# WalkerStalkerv0.net
KiCad netlist of a schematic drawn in EAGLE
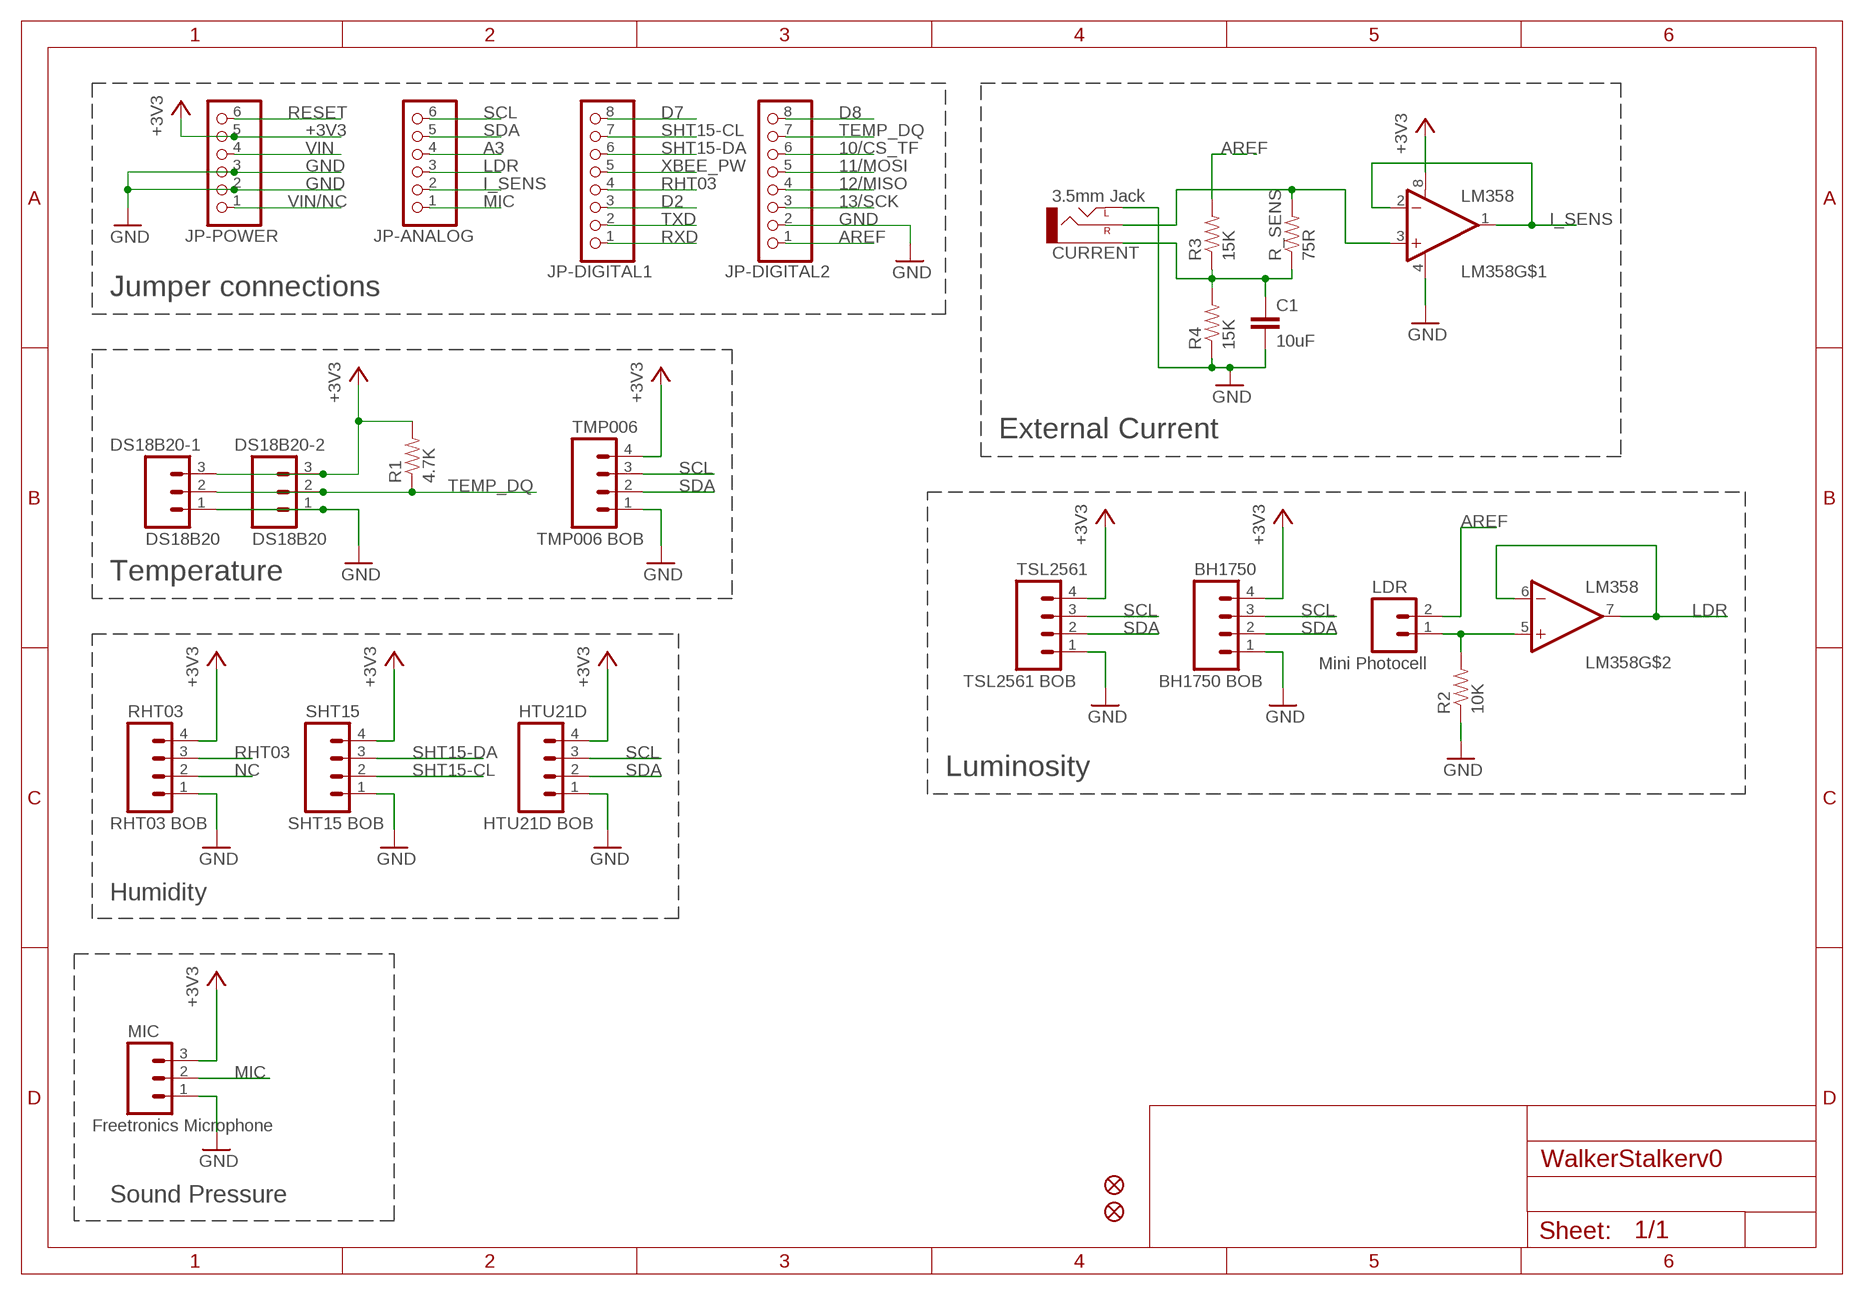
[diagram p0: schematic, sheet 1]

(export (version "E")
  (design (tool "Eeschema 10.0.6"))
  (components
    (comp (ref "BH1750")
      (value "BH1750 BOB")
      (footprint "eagle-import:MOLEX-1X4")
      (libsource (lib "eagle-import") (part "M04POLAR"))
    )
    (comp (ref "C1")
      (value "10uF")
      (footprint "eagle-import:1206")
      (libsource (lib "eagle-import") (part "CAP1206"))
    )
    (comp (ref "CURRENT")
      (value "3.5mm Jack")
      (footprint "eagle-import:AUDIO-JACK")
      (libsource (lib "eagle-import") (part "AUDIO-JACKPTH"))
    )
    (comp (ref "DS18B20-1")
      (value "DS18B20")
      (footprint "eagle-import:MOLEX-1X3")
      (libsource (lib "eagle-import") (part "M03POLAR"))
    )
    (comp (ref "DS18B20-2")
      (value "DS18B20")
      (footprint "eagle-import:MOLEX-1X3")
      (libsource (lib "eagle-import") (part "M03POLAR"))
    )
    (comp (ref "FID1")
      (value "FIDUCIAL1.5X3")
      (footprint "eagle-import:FIDUCIAL-1.5X3")
      (libsource (lib "eagle-import") (part "FIDUCIAL1.5X3"))
    )
    (comp (ref "FID2")
      (value "FIDUCIAL1.5X3")
      (footprint "eagle-import:FIDUCIAL-1.5X3")
      (libsource (lib "eagle-import") (part "FIDUCIAL1.5X3"))
    )
    (comp (ref "HTU21D")
      (value "HTU21D BOB")
      (footprint "eagle-import:MOLEX-1X4")
      (libsource (lib "eagle-import") (part "M04POLAR"))
    )
    (comp (ref "JP-ANALOG")
      (value "PINHD-1X6CB")
      (footprint "eagle-import:1X06-CLEANBIG")
      (libsource (lib "eagle-import") (part "PINHD-1X6CB"))
    )
    (comp (ref "JP-DIGITAL1")
      (value "PINHD-1X8CLEANBIG")
      (footprint "eagle-import:1X08-CLEANBIG")
      (libsource (lib "eagle-import") (part "PINHD-1X8CLEANBIG"))
    )
    (comp (ref "JP-DIGITAL2")
      (value "PINHD-1X8CLEANBIG")
      (footprint "eagle-import:1X08-CLEANBIG")
      (libsource (lib "eagle-import") (part "PINHD-1X8CLEANBIG"))
    )
    (comp (ref "JP-POWER")
      (value "PINHD-1X6CB")
      (footprint "eagle-import:1X06-CLEANBIG")
      (libsource (lib "eagle-import") (part "PINHD-1X6CB"))
    )
    (comp (ref "LDR")
      (value "Mini Photocell")
      (footprint "eagle-import:MOLEX-1X2")
      (libsource (lib "eagle-import") (part "M02POLAR"))
    )
    (comp (ref "LM358")
      (value "LM358")
      (footprint "eagle-import:DIP08")
      (libsource (lib "eagle-import") (part "LM358"))
    )
    (comp (ref "MIC")
      (value "Freetronics Microphone")
      (footprint "eagle-import:MOLEX-1X3")
      (libsource (lib "eagle-import") (part "M03POLAR"))
    )
    (comp (ref "R1")
      (value "4.7K")
      (footprint "eagle-import:1206")
      (libsource (lib "eagle-import") (part "RESISTOR1206"))
    )
    (comp (ref "R2")
      (value "10K")
      (footprint "eagle-import:1206")
      (libsource (lib "eagle-import") (part "RESISTOR1206"))
    )
    (comp (ref "R3")
      (value "15K")
      (footprint "eagle-import:1206")
      (libsource (lib "eagle-import") (part "RESISTOR1206"))
    )
    (comp (ref "R4")
      (value "15K")
      (footprint "eagle-import:1206")
      (libsource (lib "eagle-import") (part "RESISTOR1206"))
    )
    (comp (ref "RHT03")
      (value "RHT03 BOB")
      (footprint "eagle-import:MOLEX-1X4")
      (libsource (lib "eagle-import") (part "M04POLAR"))
    )
    (comp (ref "R_SENS")
      (value "75R")
      (footprint "eagle-import:1206")
      (libsource (lib "eagle-import") (part "RESISTOR1206"))
    )
    (comp (ref "SHT15")
      (value "SHT15 BOB")
      (footprint "eagle-import:MOLEX-1X4")
      (libsource (lib "eagle-import") (part "M04POLAR"))
    )
    (comp (ref "TMP006")
      (value "TMP006 BOB")
      (footprint "eagle-import:MOLEX-1X4")
      (libsource (lib "eagle-import") (part "M04POLAR"))
    )
    (comp (ref "TSL2561")
      (value "TSL2561 BOB")
      (footprint "eagle-import:MOLEX-1X4")
      (libsource (lib "eagle-import") (part "M04POLAR"))
    )
  )
  (nets
    (net (code "1") (name "+3V3") (class "Default")
      (node (ref "BH1750") (pin "4") (pinfunction "4_4") (pintype "passive"))
      (node (ref "DS18B20-1") (pin "3") (pinfunction "3_3") (pintype "passive"))
      (node (ref "DS18B20-2") (pin "3") (pinfunction "3_3") (pintype "passive"))
      (node (ref "HTU21D") (pin "4") (pinfunction "4_4") (pintype "passive"))
      (node (ref "JP-POWER") (pin "5") (pinfunction "5_5") (pintype "passive"))
      (node (ref "LM358") (pin "8") (pinfunction "V+_8") (pintype "power_in"))
      (node (ref "MIC") (pin "3") (pinfunction "3_3") (pintype "passive"))
      (node (ref "R1") (pin "2") (pinfunction "2_2") (pintype "passive"))
      (node (ref "RHT03") (pin "4") (pinfunction "4_4") (pintype "passive"))
      (node (ref "SHT15") (pin "4") (pinfunction "4_4") (pintype "passive"))
      (node (ref "TMP006") (pin "4") (pinfunction "4_4") (pintype "passive"))
      (node (ref "TSL2561") (pin "4") (pinfunction "4_4") (pintype "passive"))
    )
    (net (code "2") (name "/10{slash}CS_TF") (class "Default")
      (node (ref "JP-DIGITAL2") (pin "6") (pinfunction "6_6") (pintype "passive"))
    )
    (net (code "3") (name "/11{slash}MOSI") (class "Default")
      (node (ref "JP-DIGITAL2") (pin "5") (pinfunction "5_5") (pintype "passive"))
    )
    (net (code "4") (name "/12{slash}MISO") (class "Default")
      (node (ref "JP-DIGITAL2") (pin "4") (pinfunction "4_4") (pintype "passive"))
    )
    (net (code "5") (name "/13{slash}SCK") (class "Default")
      (node (ref "JP-DIGITAL2") (pin "3") (pinfunction "3_3") (pintype "passive"))
    )
    (net (code "6") (name "/A3") (class "Default")
      (node (ref "JP-ANALOG") (pin "4") (pinfunction "4_4") (pintype "passive"))
    )
    (net (code "7") (name "/AREF") (class "Default")
      (node (ref "JP-DIGITAL2") (pin "1") (pinfunction "1_1") (pintype "passive"))
      (node (ref "LDR") (pin "2") (pinfunction "2_2") (pintype "passive"))
      (node (ref "R3") (pin "2") (pinfunction "2_2") (pintype "passive"))
    )
    (net (code "8") (name "/D2") (class "Default")
      (node (ref "JP-DIGITAL1") (pin "3") (pinfunction "3_3") (pintype "passive"))
    )
    (net (code "9") (name "/D7") (class "Default")
      (node (ref "JP-DIGITAL1") (pin "8") (pinfunction "8_8") (pintype "passive"))
    )
    (net (code "10") (name "/D8") (class "Default")
      (node (ref "JP-DIGITAL2") (pin "8") (pinfunction "8_8") (pintype "passive"))
    )
    (net (code "11") (name "/I_SENS") (class "Default")
      (node (ref "JP-ANALOG") (pin "2") (pinfunction "2_2") (pintype "passive"))
      (node (ref "LM358") (pin "1") (pinfunction "OUT_1") (pintype "output"))
      (node (ref "LM358") (pin "2") (pinfunction "-IN_2") (pintype "input"))
    )
    (net (code "12") (name "/LDR") (class "Default")
      (node (ref "JP-ANALOG") (pin "3") (pinfunction "3_3") (pintype "passive"))
      (node (ref "LM358") (pin "6") (pinfunction "-IN_6") (pintype "input"))
      (node (ref "LM358") (pin "7") (pinfunction "OUT_7") (pintype "output"))
    )
    (net (code "13") (name "/MIC") (class "Default")
      (node (ref "JP-ANALOG") (pin "1") (pinfunction "1_1") (pintype "passive"))
      (node (ref "MIC") (pin "2") (pinfunction "2_2") (pintype "passive"))
    )
    (net (code "14") (name "/NC") (class "Default")
      (node (ref "RHT03") (pin "2") (pinfunction "2_2") (pintype "passive"))
    )
    (net (code "15") (name "/RESET") (class "Default")
      (node (ref "JP-POWER") (pin "6") (pinfunction "6_6") (pintype "passive"))
    )
    (net (code "16") (name "/RHT03") (class "Default")
      (node (ref "JP-DIGITAL1") (pin "4") (pinfunction "4_4") (pintype "passive"))
      (node (ref "RHT03") (pin "3") (pinfunction "3_3") (pintype "passive"))
    )
    (net (code "17") (name "/RXD") (class "Default")
      (node (ref "JP-DIGITAL1") (pin "1") (pinfunction "1_1") (pintype "passive"))
    )
    (net (code "18") (name "/SCL") (class "Default")
      (node (ref "BH1750") (pin "3") (pinfunction "3_3") (pintype "passive"))
      (node (ref "HTU21D") (pin "3") (pinfunction "3_3") (pintype "passive"))
      (node (ref "JP-ANALOG") (pin "6") (pinfunction "6_6") (pintype "passive"))
      (node (ref "TMP006") (pin "3") (pinfunction "3_3") (pintype "passive"))
      (node (ref "TSL2561") (pin "3") (pinfunction "3_3") (pintype "passive"))
    )
    (net (code "19") (name "/SDA") (class "Default")
      (node (ref "BH1750") (pin "2") (pinfunction "2_2") (pintype "passive"))
      (node (ref "HTU21D") (pin "2") (pinfunction "2_2") (pintype "passive"))
      (node (ref "JP-ANALOG") (pin "5") (pinfunction "5_5") (pintype "passive"))
      (node (ref "TMP006") (pin "2") (pinfunction "2_2") (pintype "passive"))
      (node (ref "TSL2561") (pin "2") (pinfunction "2_2") (pintype "passive"))
    )
    (net (code "20") (name "/SHT15-CL") (class "Default")
      (node (ref "JP-DIGITAL1") (pin "7") (pinfunction "7_7") (pintype "passive"))
      (node (ref "SHT15") (pin "2") (pinfunction "2_2") (pintype "passive"))
    )
    (net (code "21") (name "/SHT15-DA") (class "Default")
      (node (ref "JP-DIGITAL1") (pin "6") (pinfunction "6_6") (pintype "passive"))
      (node (ref "SHT15") (pin "3") (pinfunction "3_3") (pintype "passive"))
    )
    (net (code "22") (name "/TEMP_DQ") (class "Default")
      (node (ref "DS18B20-1") (pin "2") (pinfunction "2_2") (pintype "passive"))
      (node (ref "DS18B20-2") (pin "2") (pinfunction "2_2") (pintype "passive"))
      (node (ref "JP-DIGITAL2") (pin "7") (pinfunction "7_7") (pintype "passive"))
      (node (ref "R1") (pin "1") (pinfunction "1_1") (pintype "passive"))
    )
    (net (code "23") (name "/TXD") (class "Default")
      (node (ref "JP-DIGITAL1") (pin "2") (pinfunction "2_2") (pintype "passive"))
    )
    (net (code "24") (name "/VIN") (class "Default")
      (node (ref "JP-POWER") (pin "4") (pinfunction "4_4") (pintype "passive"))
    )
    (net (code "25") (name "/VIN{slash}NC") (class "Default")
      (node (ref "JP-POWER") (pin "1") (pinfunction "1_1") (pintype "passive"))
    )
    (net (code "26") (name "/XBEE_PW") (class "Default")
      (node (ref "JP-DIGITAL1") (pin "5") (pinfunction "5_5") (pintype "passive"))
    )
    (net (code "27") (name "GND") (class "Default")
      (node (ref "BH1750") (pin "1") (pinfunction "1_1") (pintype "passive"))
      (node (ref "C1") (pin "2") (pinfunction "2_2") (pintype "passive"))
      (node (ref "CURRENT") (pin "TIP") (pinfunction "LEFT_TIP") (pintype "bidirectional"))
      (node (ref "DS18B20-1") (pin "1") (pinfunction "1_1") (pintype "passive"))
      (node (ref "DS18B20-2") (pin "1") (pinfunction "1_1") (pintype "passive"))
      (node (ref "HTU21D") (pin "1") (pinfunction "1_1") (pintype "passive"))
      (node (ref "JP-DIGITAL2") (pin "2") (pinfunction "2_2") (pintype "passive"))
      (node (ref "JP-POWER") (pin "2") (pinfunction "2_2") (pintype "passive"))
      (node (ref "JP-POWER") (pin "3") (pinfunction "3_3") (pintype "passive"))
      (node (ref "LM358") (pin "4") (pinfunction "V-_4") (pintype "power_in"))
      (node (ref "MIC") (pin "1") (pinfunction "1_1") (pintype "passive"))
      (node (ref "R2") (pin "1") (pinfunction "1_1") (pintype "passive"))
      (node (ref "R4") (pin "1") (pinfunction "1_1") (pintype "passive"))
      (node (ref "RHT03") (pin "1") (pinfunction "1_1") (pintype "passive"))
      (node (ref "SHT15") (pin "1") (pinfunction "1_1") (pintype "passive"))
      (node (ref "TMP006") (pin "1") (pinfunction "1_1") (pintype "passive"))
      (node (ref "TSL2561") (pin "1") (pinfunction "1_1") (pintype "passive"))
    )
    (net (code "28") (name "Net-(C1-Pad1)") (class "Default")
      (node (ref "C1") (pin "1") (pinfunction "1_1") (pintype "passive"))
      (node (ref "CURRENT") (pin "SLEEVE") (pinfunction "SLEEVE_SLEEVE") (pintype "bidirectional"))
      (node (ref "R3") (pin "1") (pinfunction "1_1") (pintype "passive"))
      (node (ref "R4") (pin "2") (pinfunction "2_2") (pintype "passive"))
      (node (ref "R_SENS") (pin "1") (pinfunction "1_1") (pintype "passive"))
    )
    (net (code "29") (name "Net-(CURRENT-RIGHT)") (class "Default")
      (node (ref "CURRENT") (pin "RING") (pinfunction "RIGHT_RING") (pintype "bidirectional"))
      (node (ref "LM358") (pin "3") (pinfunction "+IN_3") (pintype "input"))
      (node (ref "R_SENS") (pin "2") (pinfunction "2_2") (pintype "passive"))
    )
    (net (code "30") (name "Net-(LM358B-+IN)") (class "Default")
      (node (ref "LDR") (pin "1") (pinfunction "1_1") (pintype "passive"))
      (node (ref "LM358") (pin "5") (pinfunction "+IN_5") (pintype "input"))
      (node (ref "R2") (pin "2") (pinfunction "2_2") (pintype "passive"))
    )
  )
)
